# design.net
KiCad netlist of a schematic drawn in EasyEDA Pro
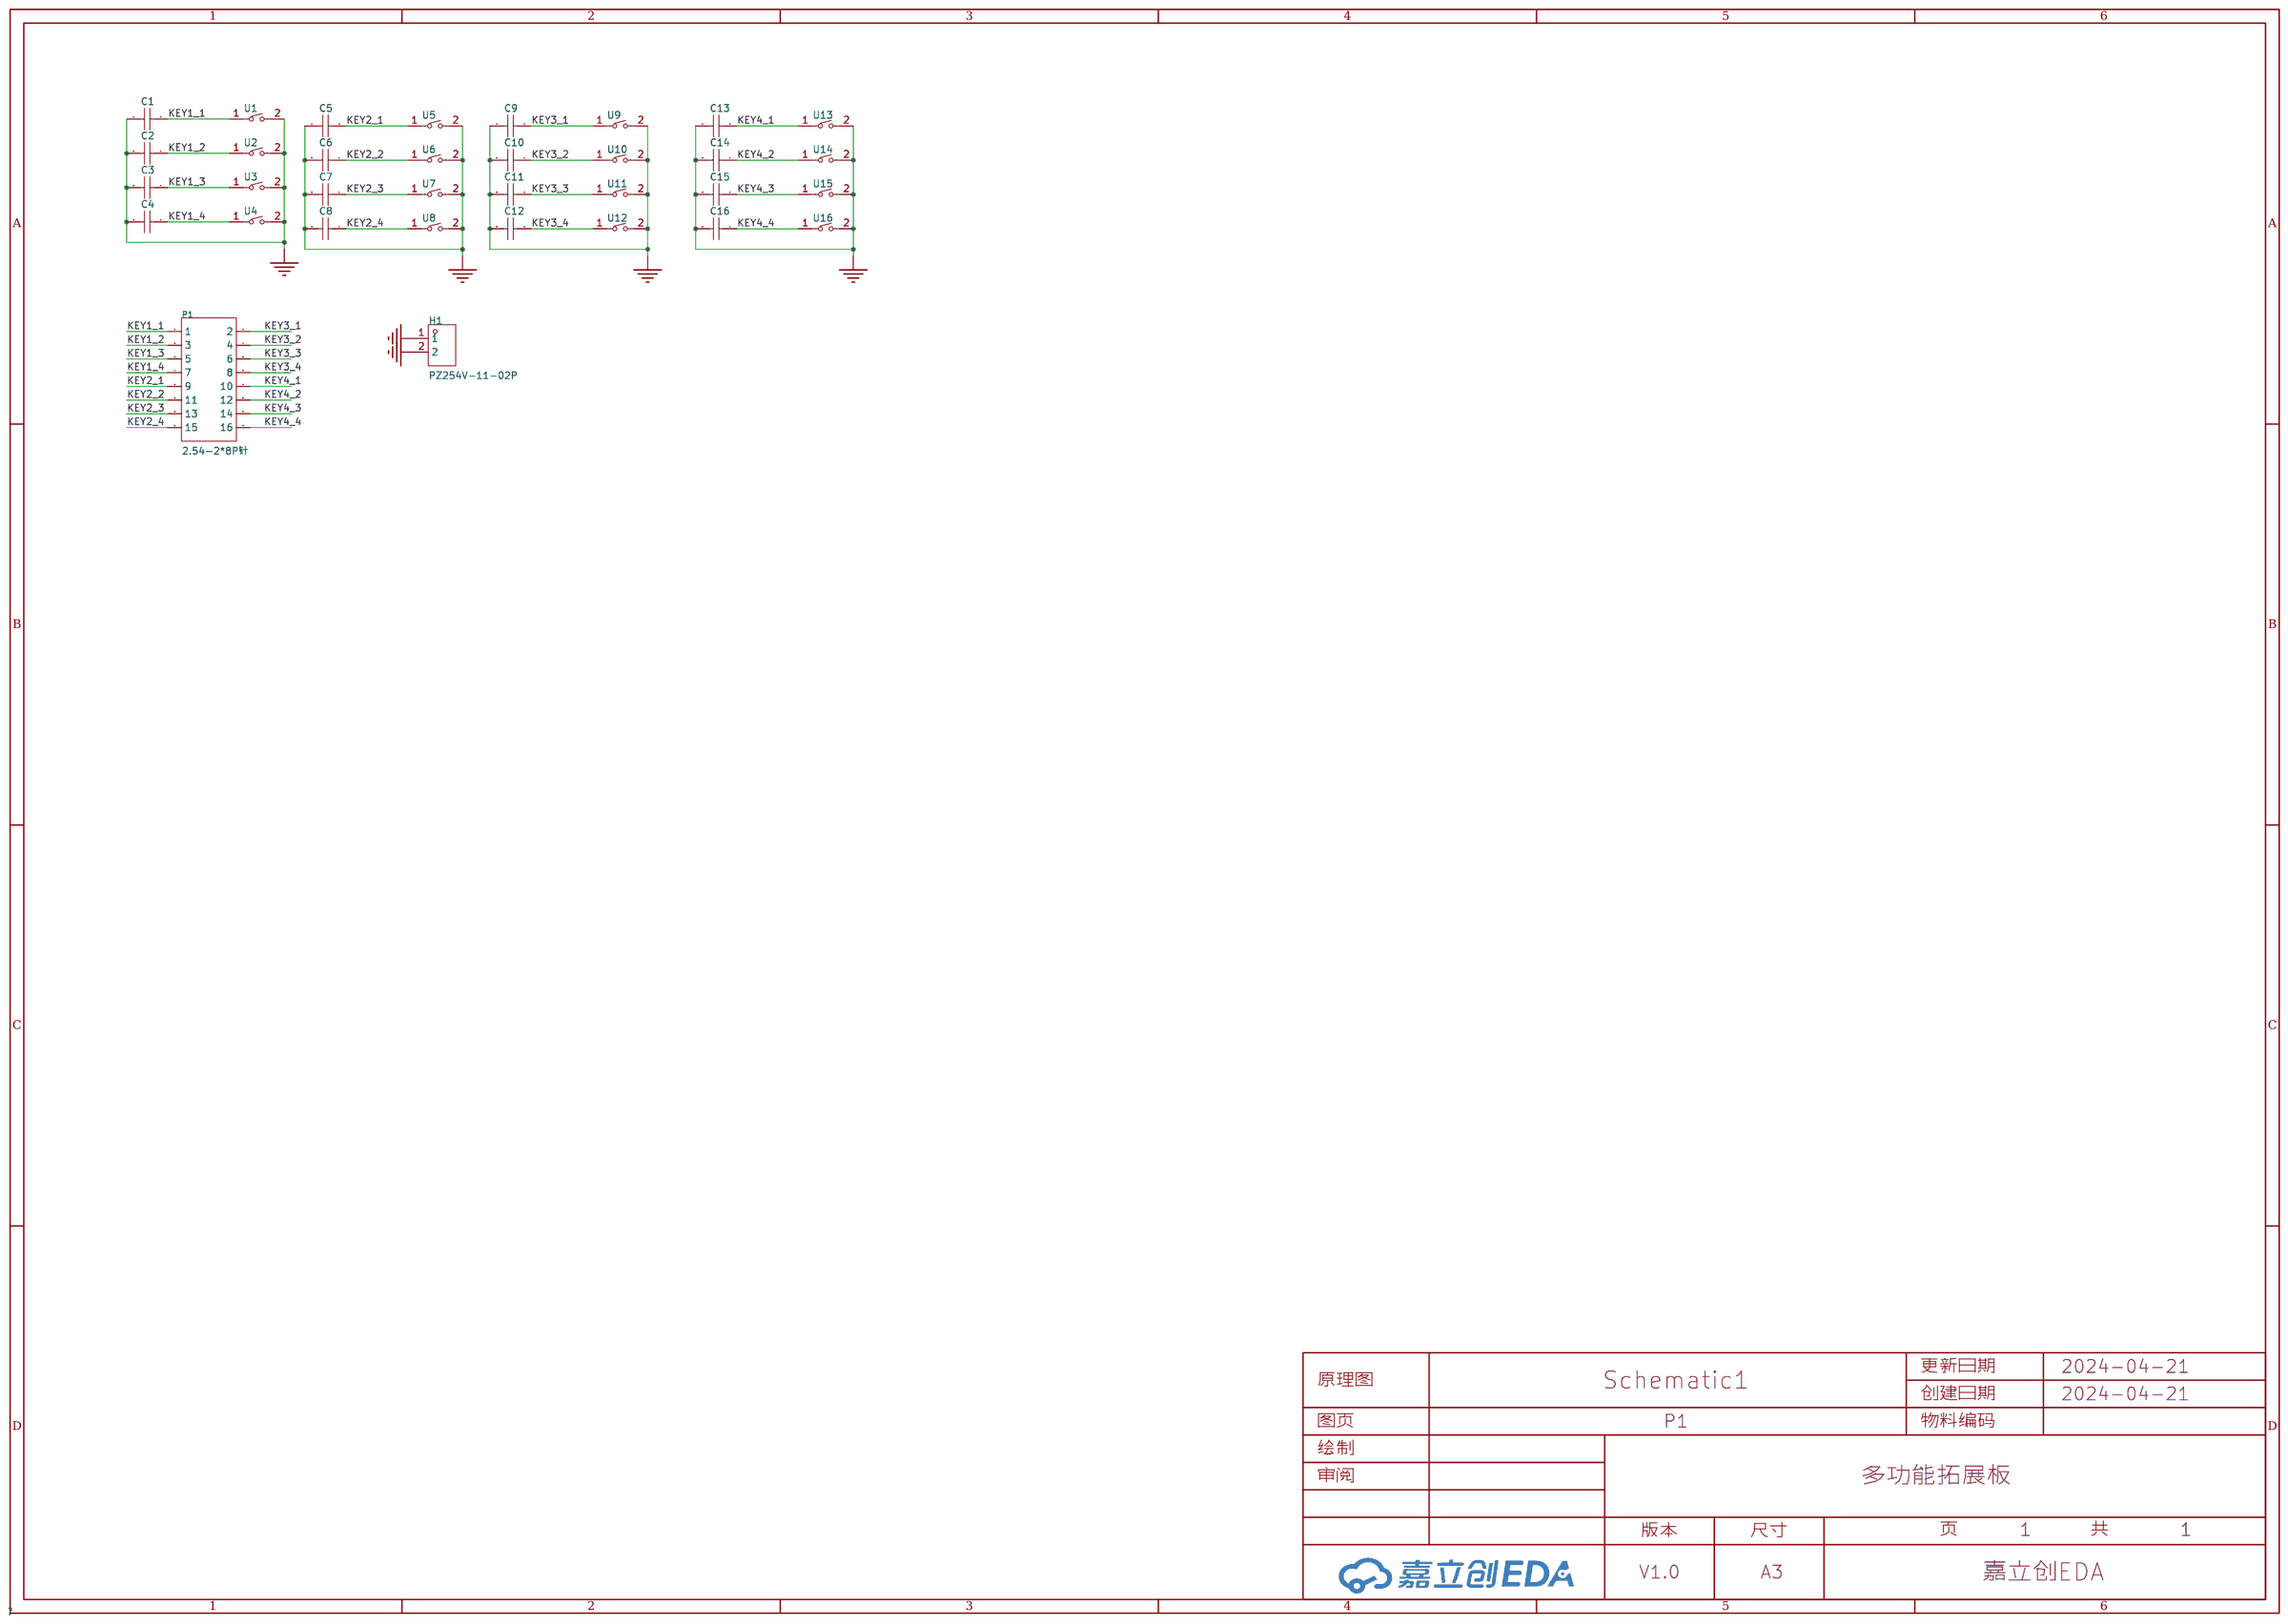
[diagram p0: schematic sheet]

(export (version "E")
  (design (tool "Eeschema 10.0.6"))
  (components
    (comp (ref "C1")
      (value "100nF")
      (footprint "easyedapro:C0805")
      (description "容值:100nF;精度:±10%;额定电压:50V;材质(温度系数):X7R;")
      (fields (field (name "Manufacturer Part") "0805B104K500NT") (field (name "Manufacturer") "FH(风华)"))
      (libsource (lib "easyedapro") (part "0805B104K500NT"))
    )
    (comp (ref "C2")
      (value "100nF")
      (footprint "easyedapro:C0805")
      (description "容值:100nF;精度:±10%;额定电压:50V;材质(温度系数):X7R;")
      (fields (field (name "Manufacturer Part") "0805B104K500NT") (field (name "Manufacturer") "FH(风华)"))
      (libsource (lib "easyedapro") (part "0805B104K500NT"))
    )
    (comp (ref "C3")
      (value "100nF")
      (footprint "easyedapro:C0805")
      (description "容值:100nF;精度:±10%;额定电压:50V;材质(温度系数):X7R;")
      (fields (field (name "Manufacturer Part") "0805B104K500NT") (field (name "Manufacturer") "FH(风华)"))
      (libsource (lib "easyedapro") (part "0805B104K500NT"))
    )
    (comp (ref "C4")
      (value "100nF")
      (footprint "easyedapro:C0805")
      (description "容值:100nF;精度:±10%;额定电压:50V;材质(温度系数):X7R;")
      (fields (field (name "Manufacturer Part") "0805B104K500NT") (field (name "Manufacturer") "FH(风华)"))
      (libsource (lib "easyedapro") (part "0805B104K500NT"))
    )
    (comp (ref "C5")
      (value "100nF")
      (footprint "easyedapro:C0805")
      (description "容值:100nF;精度:±10%;额定电压:50V;材质(温度系数):X7R;")
      (fields (field (name "Manufacturer Part") "0805B104K500NT") (field (name "Manufacturer") "FH(风华)"))
      (libsource (lib "easyedapro") (part "0805B104K500NT"))
    )
    (comp (ref "C6")
      (value "100nF")
      (footprint "easyedapro:C0805")
      (description "容值:100nF;精度:±10%;额定电压:50V;材质(温度系数):X7R;")
      (fields (field (name "Manufacturer Part") "0805B104K500NT") (field (name "Manufacturer") "FH(风华)"))
      (libsource (lib "easyedapro") (part "0805B104K500NT"))
    )
    (comp (ref "C7")
      (value "100nF")
      (footprint "easyedapro:C0805")
      (description "容值:100nF;精度:±10%;额定电压:50V;材质(温度系数):X7R;")
      (fields (field (name "Manufacturer Part") "0805B104K500NT") (field (name "Manufacturer") "FH(风华)"))
      (libsource (lib "easyedapro") (part "0805B104K500NT"))
    )
    (comp (ref "C8")
      (value "100nF")
      (footprint "easyedapro:C0805")
      (description "容值:100nF;精度:±10%;额定电压:50V;材质(温度系数):X7R;")
      (fields (field (name "Manufacturer Part") "0805B104K500NT") (field (name "Manufacturer") "FH(风华)"))
      (libsource (lib "easyedapro") (part "0805B104K500NT"))
    )
    (comp (ref "C9")
      (value "100nF")
      (footprint "easyedapro:C0805")
      (description "容值:100nF;精度:±10%;额定电压:50V;材质(温度系数):X7R;")
      (fields (field (name "Manufacturer Part") "0805B104K500NT") (field (name "Manufacturer") "FH(风华)"))
      (libsource (lib "easyedapro") (part "0805B104K500NT"))
    )
    (comp (ref "C10")
      (value "100nF")
      (footprint "easyedapro:C0805")
      (description "容值:100nF;精度:±10%;额定电压:50V;材质(温度系数):X7R;")
      (fields (field (name "Manufacturer Part") "0805B104K500NT") (field (name "Manufacturer") "FH(风华)"))
      (libsource (lib "easyedapro") (part "0805B104K500NT"))
    )
    (comp (ref "C11")
      (value "100nF")
      (footprint "easyedapro:C0805")
      (description "容值:100nF;精度:±10%;额定电压:50V;材质(温度系数):X7R;")
      (fields (field (name "Manufacturer Part") "0805B104K500NT") (field (name "Manufacturer") "FH(风华)"))
      (libsource (lib "easyedapro") (part "0805B104K500NT"))
    )
    (comp (ref "C12")
      (value "100nF")
      (footprint "easyedapro:C0805")
      (description "容值:100nF;精度:±10%;额定电压:50V;材质(温度系数):X7R;")
      (fields (field (name "Manufacturer Part") "0805B104K500NT") (field (name "Manufacturer") "FH(风华)"))
      (libsource (lib "easyedapro") (part "0805B104K500NT"))
    )
    (comp (ref "C13")
      (value "100nF")
      (footprint "easyedapro:C0805")
      (description "容值:100nF;精度:±10%;额定电压:50V;材质(温度系数):X7R;")
      (fields (field (name "Manufacturer Part") "0805B104K500NT") (field (name "Manufacturer") "FH(风华)"))
      (libsource (lib "easyedapro") (part "0805B104K500NT"))
    )
    (comp (ref "C14")
      (value "100nF")
      (footprint "easyedapro:C0805")
      (description "容值:100nF;精度:±10%;额定电压:50V;材质(温度系数):X7R;")
      (fields (field (name "Manufacturer Part") "0805B104K500NT") (field (name "Manufacturer") "FH(风华)"))
      (libsource (lib "easyedapro") (part "0805B104K500NT"))
    )
    (comp (ref "C15")
      (value "100nF")
      (footprint "easyedapro:C0805")
      (description "容值:100nF;精度:±10%;额定电压:50V;材质(温度系数):X7R;")
      (fields (field (name "Manufacturer Part") "0805B104K500NT") (field (name "Manufacturer") "FH(风华)"))
      (libsource (lib "easyedapro") (part "0805B104K500NT"))
    )
    (comp (ref "C16")
      (value "100nF")
      (footprint "easyedapro:C0805")
      (description "容值:100nF;精度:±10%;额定电压:50V;材质(温度系数):X7R;")
      (fields (field (name "Manufacturer Part") "0805B104K500NT") (field (name "Manufacturer") "FH(风华)"))
      (libsource (lib "easyedapro") (part "0805B104K500NT"))
    )
    (comp (ref "H1")
      (value "PZ254V-11-02P")
      (footprint "easyedapro:HDR-TH_2P-P2.54-V-M")
      (fields (field (name "Manufacturer") "XFCN(兴飞)"))
      (libsource (lib "easyedapro") (part "PZ254V-11-02P"))
    )
    (comp (ref "P1")
      (value "2.54-2*8P针")
      (footprint "easyedapro:HDR-TH_16P-P2.54-V-M-R2-C8-S2.54")
      (fields (field (name "Manufacturer") "BOOMELE(博穆精密)"))
      (libsource (lib "easyedapro") (part "Header-Male-2.54_2x8"))
    )
    (comp (ref "U1")
      (value "ZX-QC36-4.3CJ")
      (footprint "easyedapro:KEY-TH_L6.0-W3.5-P6.50")
      (fields (field (name "Manufacturer") "Megastar(兆星)"))
      (libsource (lib "easyedapro") (part "ZX-QC36-4.3CJ"))
    )
    (comp (ref "U2")
      (value "ZX-QC36-4.3CJ")
      (footprint "easyedapro:KEY-TH_L6.0-W3.5-P6.50")
      (fields (field (name "Manufacturer") "Megastar(兆星)"))
      (libsource (lib "easyedapro") (part "ZX-QC36-4.3CJ"))
    )
    (comp (ref "U3")
      (value "ZX-QC36-4.3CJ")
      (footprint "easyedapro:KEY-TH_L6.0-W3.5-P6.50")
      (fields (field (name "Manufacturer") "Megastar(兆星)"))
      (libsource (lib "easyedapro") (part "ZX-QC36-4.3CJ"))
    )
    (comp (ref "U4")
      (value "ZX-QC36-4.3CJ")
      (footprint "easyedapro:KEY-TH_L6.0-W3.5-P6.50")
      (fields (field (name "Manufacturer") "Megastar(兆星)"))
      (libsource (lib "easyedapro") (part "ZX-QC36-4.3CJ"))
    )
    (comp (ref "U5")
      (value "ZX-QC36-4.3CJ")
      (footprint "easyedapro:KEY-TH_L6.0-W3.5-P6.50")
      (fields (field (name "Manufacturer") "Megastar(兆星)"))
      (libsource (lib "easyedapro") (part "ZX-QC36-4.3CJ"))
    )
    (comp (ref "U6")
      (value "ZX-QC36-4.3CJ")
      (footprint "easyedapro:KEY-TH_L6.0-W3.5-P6.50")
      (fields (field (name "Manufacturer") "Megastar(兆星)"))
      (libsource (lib "easyedapro") (part "ZX-QC36-4.3CJ"))
    )
    (comp (ref "U7")
      (value "ZX-QC36-4.3CJ")
      (footprint "easyedapro:KEY-TH_L6.0-W3.5-P6.50")
      (fields (field (name "Manufacturer") "Megastar(兆星)"))
      (libsource (lib "easyedapro") (part "ZX-QC36-4.3CJ"))
    )
    (comp (ref "U8")
      (value "ZX-QC36-4.3CJ")
      (footprint "easyedapro:KEY-TH_L6.0-W3.5-P6.50")
      (fields (field (name "Manufacturer") "Megastar(兆星)"))
      (libsource (lib "easyedapro") (part "ZX-QC36-4.3CJ"))
    )
    (comp (ref "U9")
      (value "ZX-QC36-4.3CJ")
      (footprint "easyedapro:KEY-TH_L6.0-W3.5-P6.50")
      (fields (field (name "Manufacturer") "Megastar(兆星)"))
      (libsource (lib "easyedapro") (part "ZX-QC36-4.3CJ"))
    )
    (comp (ref "U10")
      (value "ZX-QC36-4.3CJ")
      (footprint "easyedapro:KEY-TH_L6.0-W3.5-P6.50")
      (fields (field (name "Manufacturer") "Megastar(兆星)"))
      (libsource (lib "easyedapro") (part "ZX-QC36-4.3CJ"))
    )
    (comp (ref "U11")
      (value "ZX-QC36-4.3CJ")
      (footprint "easyedapro:KEY-TH_L6.0-W3.5-P6.50")
      (fields (field (name "Manufacturer") "Megastar(兆星)"))
      (libsource (lib "easyedapro") (part "ZX-QC36-4.3CJ"))
    )
    (comp (ref "U12")
      (value "ZX-QC36-4.3CJ")
      (footprint "easyedapro:KEY-TH_L6.0-W3.5-P6.50")
      (fields (field (name "Manufacturer") "Megastar(兆星)"))
      (libsource (lib "easyedapro") (part "ZX-QC36-4.3CJ"))
    )
    (comp (ref "U13")
      (value "ZX-QC36-4.3CJ")
      (footprint "easyedapro:KEY-TH_L6.0-W3.5-P6.50")
      (fields (field (name "Manufacturer") "Megastar(兆星)"))
      (libsource (lib "easyedapro") (part "ZX-QC36-4.3CJ"))
    )
    (comp (ref "U14")
      (value "ZX-QC36-4.3CJ")
      (footprint "easyedapro:KEY-TH_L6.0-W3.5-P6.50")
      (fields (field (name "Manufacturer") "Megastar(兆星)"))
      (libsource (lib "easyedapro") (part "ZX-QC36-4.3CJ"))
    )
    (comp (ref "U15")
      (value "ZX-QC36-4.3CJ")
      (footprint "easyedapro:KEY-TH_L6.0-W3.5-P6.50")
      (fields (field (name "Manufacturer") "Megastar(兆星)"))
      (libsource (lib "easyedapro") (part "ZX-QC36-4.3CJ"))
    )
    (comp (ref "U16")
      (value "ZX-QC36-4.3CJ")
      (footprint "easyedapro:KEY-TH_L6.0-W3.5-P6.50")
      (fields (field (name "Manufacturer") "Megastar(兆星)"))
      (libsource (lib "easyedapro") (part "ZX-QC36-4.3CJ"))
    )
  )
  (nets
    (net (code "1") (name "/KEY1_1") (class "Default")
      (node (ref "C1") (pin "2") (pinfunction "2_2") (pintype "input"))
      (node (ref "P1") (pin "1") (pinfunction "1_1") (pintype "input"))
      (node (ref "U1") (pin "1") (pinfunction "1_1") (pintype "unspecified"))
    )
    (net (code "2") (name "/KEY1_2") (class "Default")
      (node (ref "C2") (pin "1") (pinfunction "1_1") (pintype "input"))
      (node (ref "P1") (pin "3") (pinfunction "3_3") (pintype "input"))
      (node (ref "U2") (pin "1") (pinfunction "1_1") (pintype "unspecified"))
    )
    (net (code "3") (name "/KEY1_3") (class "Default")
      (node (ref "C3") (pin "1") (pinfunction "1_1") (pintype "input"))
      (node (ref "P1") (pin "5") (pinfunction "5_5") (pintype "input"))
      (node (ref "U3") (pin "1") (pinfunction "1_1") (pintype "unspecified"))
    )
    (net (code "4") (name "/KEY1_4") (class "Default")
      (node (ref "C4") (pin "1") (pinfunction "1_1") (pintype "input"))
      (node (ref "P1") (pin "7") (pinfunction "7_7") (pintype "input"))
      (node (ref "U4") (pin "1") (pinfunction "1_1") (pintype "unspecified"))
    )
    (net (code "5") (name "/KEY2_1") (class "Default")
      (node (ref "C5") (pin "2") (pinfunction "2_2") (pintype "input"))
      (node (ref "P1") (pin "9") (pinfunction "9_9") (pintype "input"))
      (node (ref "U5") (pin "1") (pinfunction "1_1") (pintype "unspecified"))
    )
    (net (code "6") (name "/KEY2_2") (class "Default")
      (node (ref "C6") (pin "1") (pinfunction "1_1") (pintype "input"))
      (node (ref "P1") (pin "11") (pinfunction "11_11") (pintype "input"))
      (node (ref "U6") (pin "1") (pinfunction "1_1") (pintype "unspecified"))
    )
    (net (code "7") (name "/KEY2_3") (class "Default")
      (node (ref "C7") (pin "1") (pinfunction "1_1") (pintype "input"))
      (node (ref "P1") (pin "13") (pinfunction "13_13") (pintype "input"))
      (node (ref "U7") (pin "1") (pinfunction "1_1") (pintype "unspecified"))
    )
    (net (code "8") (name "/KEY2_4") (class "Default")
      (node (ref "C8") (pin "1") (pinfunction "1_1") (pintype "input"))
      (node (ref "P1") (pin "15") (pinfunction "15_15") (pintype "input"))
      (node (ref "U8") (pin "1") (pinfunction "1_1") (pintype "unspecified"))
    )
    (net (code "9") (name "/KEY3_1") (class "Default")
      (node (ref "C9") (pin "2") (pinfunction "2_2") (pintype "input"))
      (node (ref "P1") (pin "2") (pinfunction "2_2") (pintype "input"))
      (node (ref "U9") (pin "1") (pinfunction "1_1") (pintype "unspecified"))
    )
    (net (code "10") (name "/KEY3_2") (class "Default")
      (node (ref "C10") (pin "1") (pinfunction "1_1") (pintype "input"))
      (node (ref "P1") (pin "4") (pinfunction "4_4") (pintype "input"))
      (node (ref "U10") (pin "1") (pinfunction "1_1") (pintype "unspecified"))
    )
    (net (code "11") (name "/KEY3_3") (class "Default")
      (node (ref "C11") (pin "1") (pinfunction "1_1") (pintype "input"))
      (node (ref "P1") (pin "6") (pinfunction "6_6") (pintype "input"))
      (node (ref "U11") (pin "1") (pinfunction "1_1") (pintype "unspecified"))
    )
    (net (code "12") (name "/KEY3_4") (class "Default")
      (node (ref "C12") (pin "1") (pinfunction "1_1") (pintype "input"))
      (node (ref "P1") (pin "8") (pinfunction "8_8") (pintype "input"))
      (node (ref "U12") (pin "1") (pinfunction "1_1") (pintype "unspecified"))
    )
    (net (code "13") (name "/KEY4_1") (class "Default")
      (node (ref "C13") (pin "2") (pinfunction "2_2") (pintype "input"))
      (node (ref "P1") (pin "10") (pinfunction "10_10") (pintype "input"))
      (node (ref "U13") (pin "1") (pinfunction "1_1") (pintype "unspecified"))
    )
    (net (code "14") (name "/KEY4_2") (class "Default")
      (node (ref "C14") (pin "1") (pinfunction "1_1") (pintype "input"))
      (node (ref "P1") (pin "12") (pinfunction "12_12") (pintype "input"))
      (node (ref "U14") (pin "1") (pinfunction "1_1") (pintype "unspecified"))
    )
    (net (code "15") (name "/KEY4_3") (class "Default")
      (node (ref "C15") (pin "1") (pinfunction "1_1") (pintype "input"))
      (node (ref "P1") (pin "14") (pinfunction "14_14") (pintype "input"))
      (node (ref "U15") (pin "1") (pinfunction "1_1") (pintype "unspecified"))
    )
    (net (code "16") (name "/KEY4_4") (class "Default")
      (node (ref "C16") (pin "1") (pinfunction "1_1") (pintype "input"))
      (node (ref "P1") (pin "16") (pinfunction "16_16") (pintype "input"))
      (node (ref "U16") (pin "1") (pinfunction "1_1") (pintype "unspecified"))
    )
    (net (code "17") (name "GND") (class "Default")
      (node (ref "C1") (pin "1") (pinfunction "1_1") (pintype "input"))
      (node (ref "C10") (pin "2") (pinfunction "2_2") (pintype "input"))
      (node (ref "C11") (pin "2") (pinfunction "2_2") (pintype "input"))
      (node (ref "C12") (pin "2") (pinfunction "2_2") (pintype "input"))
      (node (ref "C13") (pin "1") (pinfunction "1_1") (pintype "input"))
      (node (ref "C14") (pin "2") (pinfunction "2_2") (pintype "input"))
      (node (ref "C15") (pin "2") (pinfunction "2_2") (pintype "input"))
      (node (ref "C16") (pin "2") (pinfunction "2_2") (pintype "input"))
      (node (ref "C2") (pin "2") (pinfunction "2_2") (pintype "input"))
      (node (ref "C3") (pin "2") (pinfunction "2_2") (pintype "input"))
      (node (ref "C4") (pin "2") (pinfunction "2_2") (pintype "input"))
      (node (ref "C5") (pin "1") (pinfunction "1_1") (pintype "input"))
      (node (ref "C6") (pin "2") (pinfunction "2_2") (pintype "input"))
      (node (ref "C7") (pin "2") (pinfunction "2_2") (pintype "input"))
      (node (ref "C8") (pin "2") (pinfunction "2_2") (pintype "input"))
      (node (ref "C9") (pin "1") (pinfunction "1_1") (pintype "input"))
      (node (ref "H1") (pin "1") (pinfunction "1_1") (pintype "unspecified"))
      (node (ref "H1") (pin "2") (pinfunction "2_2") (pintype "unspecified"))
      (node (ref "U1") (pin "2") (pinfunction "2_2") (pintype "unspecified"))
      (node (ref "U10") (pin "2") (pinfunction "2_2") (pintype "unspecified"))
      (node (ref "U11") (pin "2") (pinfunction "2_2") (pintype "unspecified"))
      (node (ref "U12") (pin "2") (pinfunction "2_2") (pintype "unspecified"))
      (node (ref "U13") (pin "2") (pinfunction "2_2") (pintype "unspecified"))
      (node (ref "U14") (pin "2") (pinfunction "2_2") (pintype "unspecified"))
      (node (ref "U15") (pin "2") (pinfunction "2_2") (pintype "unspecified"))
      (node (ref "U16") (pin "2") (pinfunction "2_2") (pintype "unspecified"))
      (node (ref "U2") (pin "2") (pinfunction "2_2") (pintype "unspecified"))
      (node (ref "U3") (pin "2") (pinfunction "2_2") (pintype "unspecified"))
      (node (ref "U4") (pin "2") (pinfunction "2_2") (pintype "unspecified"))
      (node (ref "U5") (pin "2") (pinfunction "2_2") (pintype "unspecified"))
      (node (ref "U6") (pin "2") (pinfunction "2_2") (pintype "unspecified"))
      (node (ref "U7") (pin "2") (pinfunction "2_2") (pintype "unspecified"))
      (node (ref "U8") (pin "2") (pinfunction "2_2") (pintype "unspecified"))
      (node (ref "U9") (pin "2") (pinfunction "2_2") (pintype "unspecified"))
    )
  )
)
